# SiLPA_HE_RF_detector.net
KiCad netlist of a schematic drawn in Altium Designer
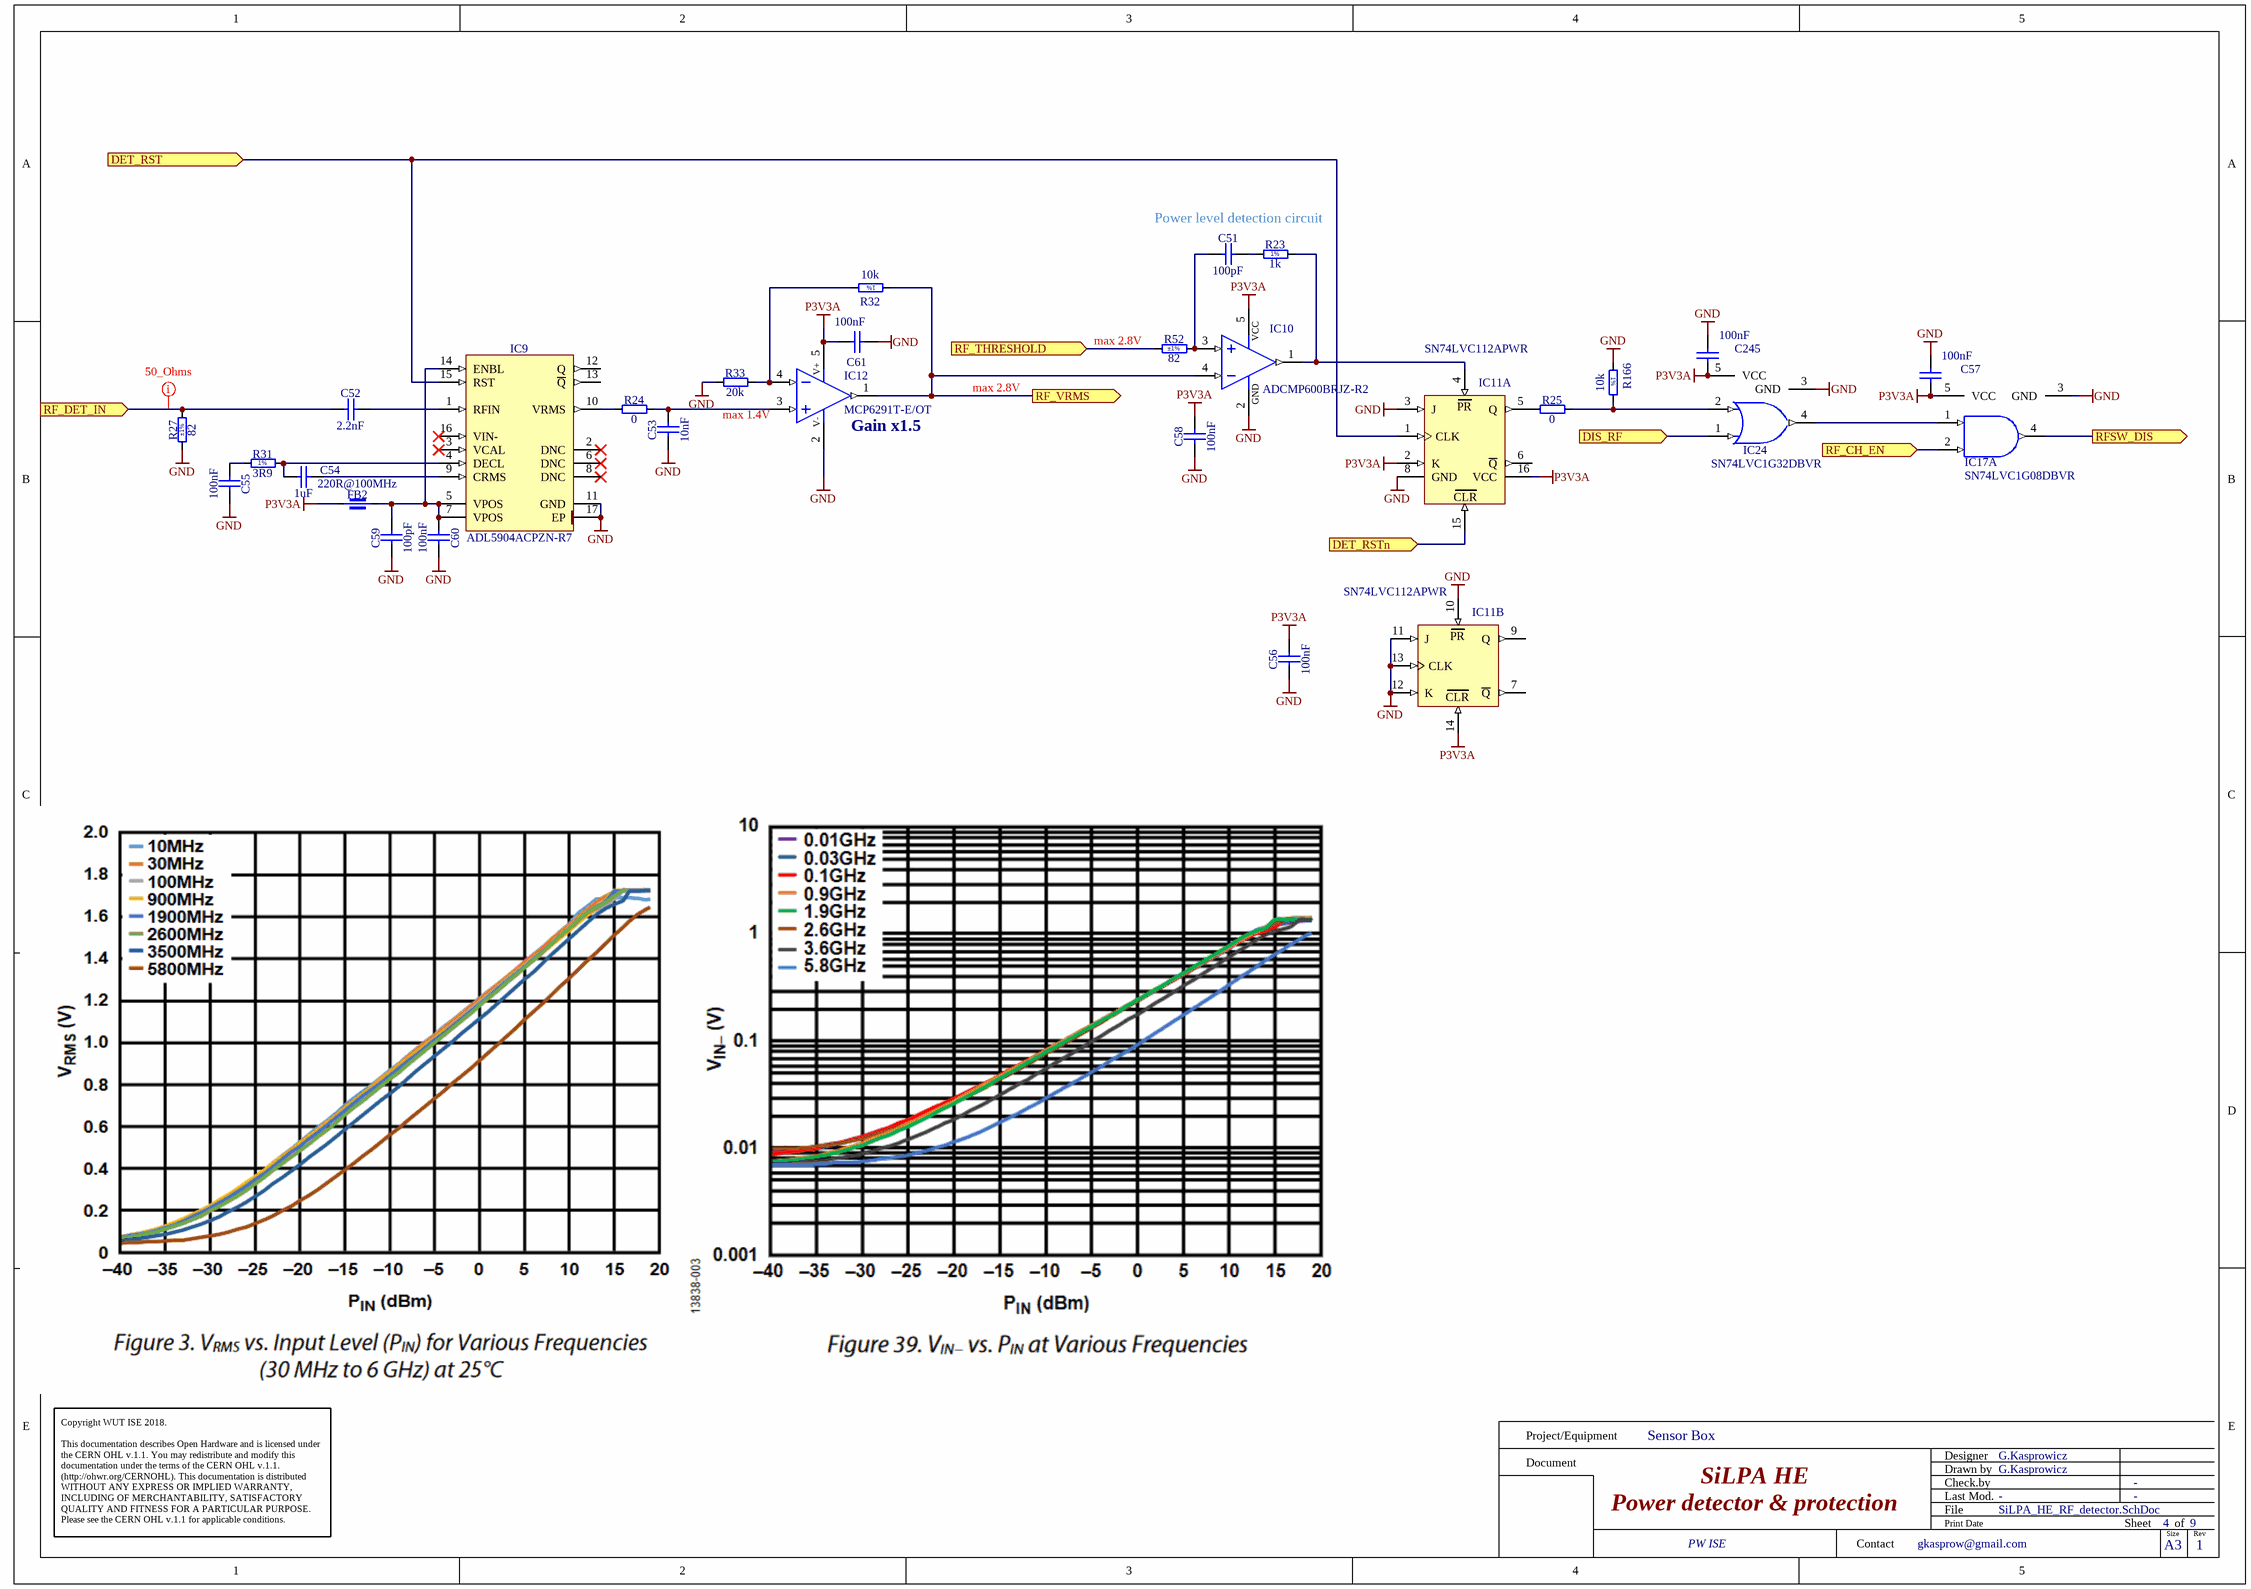
[diagram p0: SiLPA_HE_RF_detector.SchDoc]

(export (version "E")
  (design (tool "Eeschema 10.0.6"))
  (components
    (comp (ref "C51")
      (value "100pF")
      (footprint "CAPC1005X55N")
      (description "Non-polarised capacitor")
      (fields
        (field (name "PART NUMBER") "CC0402_100PF_50V_5%_C0G")
        (field (name "VOLTAGE") "50V")
        (field (name "AUTHOR") "CERN DEM JLC")
      )
      (libsource (lib "Capacitors") (part "Capacitor - non polarized"))
    )
    (comp (ref "C52")
      (value "2.2nF")
      (footprint "CAPC1608X87N")
      (description "Non-polarised capacitor")
      (fields
        (field (name "MANUFACTURER") "GENERIC")
        (field (name "MANUFACTURER PART NUMBER") "CC0603_2.2NF_50V_5%_C0G")
        (field (name "AUTHOR") "CERN DEM JMW")
      )
      (libsource (lib "Capacitors") (part "Capacitor - non polarized"))
    )
    (comp (ref "C53")
      (value "10nF")
      (footprint "CAPC1005X55N")
      (description "Non-polarised capacitor")
      (fields
        (field (name "MANUFACTURER") "GENERIC")
        (field (name "MANUFACTURER PART NUMBER") "CC0402_10NF_25V_10%_X7R")
        (field (name "AUTHOR") "CERN DEM JLC")
      )
      (libsource (lib "Capacitors") (part "Capacitor - non polarized"))
    )
    (comp (ref "C54")
      (value "1uF")
      (footprint "CAPC1608X87N")
      (description "Non-polarised capacitor")
      (fields
        (field (name "PART NUMBER") "CC0603_1UF_25V_10%_X7R")
        (field (name "VOLTAGE") "25V")
        (field (name "AUTHOR") "CERN DEM JLC")
      )
      (libsource (lib "SiLPA_HE") (part "CC0603_1UF_25V_10%_X7R"))
    )
    (comp (ref "C55")
      (value "100nF")
      (footprint "CAPC1005X55N")
      (description "Non-polarised capacitor")
      (fields
        (field (name "MANUFACTURER") "GENERIC")
        (field (name "MANUFACTURER PART NUMBER") "CC0402_100NF_50V_10%_X7R")
        (field (name "AUTHOR") "CERN DEM MR")
      )
      (libsource (lib "Capacitors") (part "Capacitor - non polarized"))
    )
    (comp (ref "C56")
      (value "100nF")
      (footprint "CAPC1005X55N")
      (description "Non-polarised capacitor")
      (fields
        (field (name "PART NUMBER") "CC0402_100NF_16V_10%_X5R")
        (field (name "VOLTAGE") "16V")
        (field (name "AUTHOR") "CERN DEM JLC")
      )
      (libsource (lib "Capacitors") (part "Capacitor - non polarized"))
    )
    (comp (ref "C57")
      (value "100nF")
      (footprint "CAPC1005X55N")
      (description "Non-polarised capacitor")
      (fields
        (field (name "PART NUMBER") "CC0402_100NF_16V_10%_X5R")
        (field (name "VOLTAGE") "16V")
        (field (name "AUTHOR") "CERN DEM JLC")
      )
      (libsource (lib "Capacitors") (part "Capacitor - non polarized"))
    )
    (comp (ref "C58")
      (value "100nF")
      (footprint "CAPC1005X55N")
      (description "Non-polarised capacitor")
      (fields
        (field (name "PART NUMBER") "CC0402_100NF_16V_10%_X5R")
        (field (name "VOLTAGE") "16V")
        (field (name "AUTHOR") "CERN DEM JLC")
      )
      (libsource (lib "Capacitors") (part "Capacitor - non polarized"))
    )
    (comp (ref "C59")
      (value "100pF")
      (footprint "CAPC1005X55N")
      (description "Non-polarised capacitor")
      (fields
        (field (name "PART NUMBER") "CC0402_100PF_50V_5%_C0G")
        (field (name "VOLTAGE") "50V")
        (field (name "AUTHOR") "CERN DEM JLC")
      )
      (libsource (lib "Capacitors") (part "Capacitor - non polarized"))
    )
    (comp (ref "C60")
      (value "100nF")
      (footprint "CAPC1005X55N")
      (description "Non-polarised capacitor")
      (fields
        (field (name "MANUFACTURER") "GENERIC")
        (field (name "MANUFACTURER PART NUMBER") "CC0402_100NF_50V_10%_X7R")
        (field (name "AUTHOR") "CERN DEM MR")
      )
      (libsource (lib "Capacitors") (part "Capacitor - non polarized"))
    )
    (comp (ref "C61")
      (value "100nF")
      (footprint "CAPC1005X55N")
      (description "Non-polarised capacitor")
      (fields
        (field (name "MANUFACTURER") "GENERIC")
        (field (name "MANUFACTURER PART NUMBER") "CC0402_100NF_16V_10%_X5R")
        (field (name "AUTHOR") "CERN DEM JLC")
      )
      (libsource (lib "Capacitors") (part "Capacitor - non polarized"))
    )
    (comp (ref "C245")
      (value "100nF")
      (footprint "CAPC1005X55N")
      (description "Non-polarised capacitor")
      (fields
        (field (name "PART NUMBER") "CC0402_100NF_16V_10%_X5R")
        (field (name "VOLTAGE") "16V")
        (field (name "AUTHOR") "CERN DEM JLC")
      )
      (libsource (lib "Capacitors") (part "Capacitor - non polarized"))
    )
    (comp (ref "FB2")
      (value "220R@100MHz")
      (footprint "INDC1005X55N")
      (fields
        (field (name "PART NUMBER") "IND0402_MURATA_BLM15HB221SN1")
        (field (name "POWER") "250mA")
        (field (name "TOLERANCE") "±25%")
        (field (name "AUTHOR") "CERN DEM JLC")
      )
      (libsource (lib "Inductors & Transformers") (part "Ferrite Bead"))
    )
    (comp (ref "IC9")
      (value "ADL5904ACPZN-R7")
      (footprint "QFN50P300X300X80-17N-S175")
      (description "DC to 6 GHz, 45 dB TruPwr Detector With Envelope Threshold Detection")
      (fields (field (name "MANUFACTURER") "ANALOG DEVICES") (field (name "AUTHOR") "CERN DEM MR"))
      (libsource (lib "ICs And Semiconductors") (part "ADL5904"))
    )
    (comp (ref "IC10")
      (value "ADCMP600BRJZ-R2")
      (footprint "SOT95P280X145-5N")
      (description "Rail-to-Rail, Very Fast, 2.5 V to 5.5 V Single-Supply TTL/CMOS Comparator")
      (fields (field (name "MANUFACTURER") "ANALOG DEVICES") (field (name "AUTHOR") "CERN DEM JLC"))
      (libsource (lib "ICs And Semiconductors") (part "ADCMP600"))
    )
    (comp (ref "IC11")
      (value "SN74LVC112APWR")
      (footprint "SOP65P640X120-16N")
      (description "Dual Negative-Edge-Triggered J-K Flip-Flop With Clear And Preset")
      (fields (field (name "MANUFACTURER") "TEXAS INSTRUMENTS") (field (name "AUTHOR") "CERN DEM JLC"))
      (libsource (lib "ICS-logic") (part "74LVC112APWR"))
    )
    (comp (ref "IC12")
      (value "MCP6291T-E/OT")
      (footprint "SOT95P270X145-5N")
      (description "Operational Amplifier")
      (fields (field (name "MANUFACTURER") "MICROCHIP TECHNOLOGY") (field (name "AUTHOR") "CERN DEM BC"))
      (libsource (lib "ICs And Semiconductors") (part "Operational Amplifier Type7"))
    )
    (comp (ref "IC17")
      (value "SN74LVC1G08DBVR")
      (footprint "DBV0005A_L")
      (description "Single 2-Input Positive-AND Gate, DBV0005A, LARGE T&R")
      (fields
        (field (name "GENERIC PART NUMBER") "SN74LVC1G08")
        (field (name "MANUFACTURER") "Texas Instruments")
      )
      (libsource (lib "Altium Content Vault") (part "TI-SN74XXX1X08-5"))
    )
    (comp (ref "IC24")
      (value "SN74LVC1G32DBVR")
      (footprint "SOT95P280X145-5N")
      (description "Single 2-Input Positive-OR Gate")
      (fields (field (name "MANUFACTURER") "TEXAS INSTRUMENTS") (field (name "AUTHOR") "CERN DEM JLC"))
      (libsource (lib "ICs And Semiconductors") (part "741G32"))
    )
    (comp (ref "R23")
      (value "1k")
      (footprint "RESC1005X40N")
      (description "Resistor - 1%")
      (fields
        (field (name "PART NUMBER") "R0402_1K_1%_0.0625W_100PPM")
        (field (name "POWER") "0.0625W")
        (field (name "AUTHOR") "CERN DEM JLC")
      )
      (libsource (lib "Resistors") (part "Resistor - 1%"))
    )
    (comp (ref "R24")
      (value "0")
      (footprint "RESC1005X40N")
      (description "Resistor")
      (fields
        (field (name "MANUFACTURER") "GENERIC")
        (field (name "MANUFACTURER PART NUMBER") "R0402_0R_JUMPER")
        (field (name "AUTHOR") "CERN DEM JLC")
      )
      (libsource (lib "Resistors") (part "Resistor"))
    )
    (comp (ref "R25")
      (value "0")
      (footprint "RESC1608X55N")
      (description "Resistor")
      (fields
        (field (name "PART NUMBER") "R0603_0R_JUMPER")
        (field (name "MANUFACTURER") "GENERIC")
        (field (name "AUTHOR") "CERN DEM JLC")
      )
      (libsource (lib "Resistors") (part "Resistor"))
    )
    (comp (ref "R27")
      (value "82")
      (footprint "RESC1608X55N")
      (description "Resistor - 1%")
      (fields
        (field (name "TOLERANCE") "±1%")
        (field (name "PART NUMBER") "R0603_82R_1%_0.1W_100PPM")
        (field (name "POWER") "0.1W")
        (field (name "AUTHOR") "CERN DEM JLC")
      )
      (libsource (lib "") (part "Resistor - 1%_1"))
    )
    (comp (ref "R31")
      (value "3R9")
      (footprint "RESC1005X40N")
      (description "Resistor - 1%")
      (fields
        (field (name "PART NUMBER") "R0402_3R9_1%_0.0625W_200PPM")
        (field (name "POWER") "0.0625W")
        (field (name "AUTHOR") "CERN DEM JLC")
      )
      (libsource (lib "Resistors") (part "Resistor - 1%"))
    )
    (comp (ref "R32")
      (value "10k")
      (footprint "RESC1005X40N")
      (description "Resistor - 1%")
      (fields
        (field (name "MANUFACTURER") "GENERIC")
        (field (name "MANUFACTURER PART NUMBER") "R0402_10K_1%_0.0625W_100PPM")
        (field (name "AUTHOR") "CERN DEM JLC")
      )
      (libsource (lib "Resistors") (part "Resistor - 1%"))
    )
    (comp (ref "R33")
      (value "20k")
      (footprint "RESC1005X40N")
      (description "Resistor - 1%")
      (fields
        (field (name "PART NUMBER") "R0402_20K_1%_0.0625W_100PPM")
        (field (name "POWER") "0.0625W")
        (field (name "AUTHOR") "CERN DEM JLC")
      )
      (libsource (lib "Resistors") (part "Resistor - 1%"))
    )
    (comp (ref "R52")
      (value "82")
      (footprint "RESC1005X40N")
      (description "Resistor - 1%")
      (fields
        (field (name "TOLERANCE") "±1%")
        (field (name "PART NUMBER") "R0402_82R_1%_0.0625W_100PPM")
        (field (name "POWER") "0.0625W")
        (field (name "AUTHOR") "CERN DEM JLC")
      )
      (libsource (lib "Resistors") (part "Resistor - 1%"))
    )
    (comp (ref "R166")
      (value "10k")
      (footprint "RESC1005X40N")
      (description "Resistor - 1%")
      (fields
        (field (name "MANUFACTURER") "GENERIC")
        (field (name "MANUFACTURER PART NUMBER") "R0402_10K_1%_0.0625W_100PPM")
        (field (name "AUTHOR") "CERN DEM JLC")
      )
      (libsource (lib "Resistors") (part "Resistor - 1%"))
    )
  )
  (nets
    (net (code "1") (name "/DET_RST") (class "Default")
      (node (ref "IC11") (pin "1") (pinfunction "CLK_1") (pintype "input"))
      (node (ref "IC9") (pin "15") (pinfunction "RST_15") (pintype "input"))
    )
    (net (code "2") (name "/DET_RSTn") (class "Default")
      (node (ref "IC11") (pin "15") (pinfunction "~{CLR}_15") (pintype "input"))
    )
    (net (code "3") (name "/DIS_RF") (class "Default")
      (node (ref "IC24") (pin "1") (pinfunction "A_1") (pintype "input"))
    )
    (net (code "4") (name "/RFSW_DIS") (class "Default")
      (node (ref "IC17") (pin "4") (pinfunction "Y_4") (pintype "output"))
    )
    (net (code "5") (name "/RF_CH_EN") (class "Default")
      (node (ref "IC17") (pin "2") (pinfunction "B_2") (pintype "input"))
    )
    (net (code "6") (name "/RF_DET_IN") (class "Default")
      (node (ref "C52") (pin "1") (pinfunction "1_1") (pintype "passive"))
      (node (ref "R27") (pin "2") (pinfunction "2_2") (pintype "passive"))
    )
    (net (code "7") (name "/RF_THRESHOLD") (class "Default")
      (node (ref "R52") (pin "1") (pinfunction "1_1") (pintype "passive"))
    )
    (net (code "8") (name "/RF_VRMS") (class "Default")
      (node (ref "IC10") (pin "4") (pinfunction "VN_4") (pintype "input"))
      (node (ref "IC12") (pin "1") (pinfunction "OUT_1") (pintype "output"))
      (node (ref "R32") (pin "1") (pinfunction "1_1") (pintype "passive"))
    )
    (net (code "9") (name "GND") (class "Default")
      (node (ref "C245") (pin "2") (pinfunction "2_2") (pintype "passive"))
      (node (ref "C53") (pin "1") (pinfunction "1_1") (pintype "passive"))
      (node (ref "C55") (pin "2") (pinfunction "2_2") (pintype "passive"))
      (node (ref "C56") (pin "1") (pinfunction "1_1") (pintype "passive"))
      (node (ref "C57") (pin "2") (pinfunction "2_2") (pintype "passive"))
      (node (ref "C58") (pin "1") (pinfunction "1_1") (pintype "passive"))
      (node (ref "C59") (pin "1") (pinfunction "1_1") (pintype "passive"))
      (node (ref "C60") (pin "2") (pinfunction "2_2") (pintype "passive"))
      (node (ref "C61") (pin "1") (pinfunction "1_1") (pintype "passive"))
      (node (ref "IC10") (pin "2") (pinfunction "GND_2") (pintype "power_in"))
      (node (ref "IC11") (pin "10") (pinfunction "~{PRE}_10") (pintype "input"))
      (node (ref "IC11") (pin "11") (pinfunction "J_11") (pintype "input"))
      (node (ref "IC11") (pin "12") (pinfunction "K_12") (pintype "input"))
      (node (ref "IC11") (pin "13") (pinfunction "CLK_13") (pintype "input"))
      (node (ref "IC11") (pin "3") (pinfunction "J_3") (pintype "input"))
      (node (ref "IC11") (pin "8") (pinfunction "GND_8") (pintype "power_in"))
      (node (ref "IC12") (pin "2") (pinfunction "V-_2") (pintype "power_in"))
      (node (ref "IC17") (pin "3") (pinfunction "GND_3") (pintype "power_in"))
      (node (ref "IC24") (pin "3") (pinfunction "GND_3") (pintype "power_in"))
      (node (ref "IC9") (pin "11") (pinfunction "GND_11") (pintype "power_in"))
      (node (ref "IC9") (pin "17") (pinfunction "EP_17") (pintype "power_in"))
      (node (ref "R166") (pin "1") (pinfunction "1_1") (pintype "passive"))
      (node (ref "R27") (pin "1") (pinfunction "1_1") (pintype "passive"))
      (node (ref "R33") (pin "1") (pinfunction "1_1") (pintype "passive"))
    )
    (net (code "10") (name "Net-(C51-Pad2)") (class "Default")
      (node (ref "C51") (pin "2") (pinfunction "2_2") (pintype "passive"))
      (node (ref "R23") (pin "1") (pinfunction "1_1") (pintype "passive"))
    )
    (net (code "11") (name "Net-(C55-Pad1)") (class "Default")
      (node (ref "C55") (pin "1") (pinfunction "1_1") (pintype "passive"))
      (node (ref "R31") (pin "1") (pinfunction "1_1") (pintype "passive"))
    )
    (net (code "12") (name "Net-(IC9-CRMS)") (class "Default")
      (node (ref "C54") (pin "2") (pinfunction "2_2") (pintype "passive"))
      (node (ref "IC9") (pin "9") (pinfunction "CRMS_9") (pintype "input"))
    )
    (net (code "13") (name "Net-(IC9-DECL)") (class "Default")
      (node (ref "C54") (pin "1") (pinfunction "1_1") (pintype "passive"))
      (node (ref "IC9") (pin "4") (pinfunction "DECL_4") (pintype "input"))
      (node (ref "R31") (pin "2") (pinfunction "2_2") (pintype "passive"))
    )
    (net (code "14") (name "Net-(IC9-ENBL)") (class "Default")
      (node (ref "C59") (pin "2") (pinfunction "2_2") (pintype "passive"))
      (node (ref "C60") (pin "1") (pinfunction "1_1") (pintype "passive"))
      (node (ref "FB2") (pin "2") (pinfunction "2_2") (pintype "passive"))
      (node (ref "IC9") (pin "14") (pinfunction "ENBL_14") (pintype "input"))
      (node (ref "IC9") (pin "5") (pinfunction "VPOS_5") (pintype "power_in"))
      (node (ref "IC9") (pin "7") (pinfunction "VPOS_7") (pintype "power_in"))
    )
    (net (code "15") (name "Net-(IC9-RFIN)") (class "Default")
      (node (ref "C52") (pin "2") (pinfunction "2_2") (pintype "passive"))
      (node (ref "IC9") (pin "1") (pinfunction "RFIN_1") (pintype "input"))
    )
    (net (code "16") (name "Net-(IC9-VRMS)") (class "Default")
      (node (ref "IC9") (pin "10") (pinfunction "VRMS_10") (pintype "output"))
      (node (ref "R24") (pin "1") (pinfunction "1_1") (pintype "passive"))
    )
    (net (code "17") (name "Net-(IC10-VP)") (class "Default")
      (node (ref "C51") (pin "1") (pinfunction "1_1") (pintype "passive"))
      (node (ref "IC10") (pin "3") (pinfunction "VP_3") (pintype "input"))
      (node (ref "R52") (pin "2") (pinfunction "2_2") (pintype "passive"))
    )
    (net (code "18") (name "Net-(IC10-q)") (class "Default")
      (node (ref "IC10") (pin "1") (pinfunction "q_1") (pintype "output"))
      (node (ref "IC11") (pin "4") (pinfunction "~{PRE}_4") (pintype "input"))
      (node (ref "R23") (pin "2") (pinfunction "2_2") (pintype "passive"))
    )
    (net (code "19") (name "Net-(IC11A-Q)") (class "Default")
      (node (ref "IC11") (pin "5") (pinfunction "Q_5") (pintype "output"))
      (node (ref "R25") (pin "1") (pinfunction "1_1") (pintype "passive"))
    )
    (net (code "20") (name "Net-(IC12-IN+)") (class "Default")
      (node (ref "C53") (pin "2") (pinfunction "2_2") (pintype "passive"))
      (node (ref "IC12") (pin "3") (pinfunction "IN+_3") (pintype "input"))
      (node (ref "R24") (pin "2") (pinfunction "2_2") (pintype "passive"))
    )
    (net (code "21") (name "Net-(IC12-IN-)") (class "Default")
      (node (ref "IC12") (pin "4") (pinfunction "IN-_4") (pintype "input"))
      (node (ref "R32") (pin "2") (pinfunction "2_2") (pintype "passive"))
      (node (ref "R33") (pin "2") (pinfunction "2_2") (pintype "passive"))
    )
    (net (code "22") (name "Net-(IC17A-A)") (class "Default")
      (node (ref "IC17") (pin "1") (pinfunction "A_1") (pintype "input"))
      (node (ref "IC24") (pin "4") (pinfunction "Y_4") (pintype "output"))
    )
    (net (code "23") (name "Net-(IC24-B)") (class "Default")
      (node (ref "IC24") (pin "2") (pinfunction "B_2") (pintype "input"))
      (node (ref "R166") (pin "2") (pinfunction "2_2") (pintype "passive"))
      (node (ref "R25") (pin "2") (pinfunction "2_2") (pintype "passive"))
    )
    (net (code "24") (name "P3V3A") (class "Default")
      (node (ref "C245") (pin "1") (pinfunction "1_1") (pintype "passive"))
      (node (ref "C56") (pin "2") (pinfunction "2_2") (pintype "passive"))
      (node (ref "C57") (pin "1") (pinfunction "1_1") (pintype "passive"))
      (node (ref "C58") (pin "2") (pinfunction "2_2") (pintype "passive"))
      (node (ref "C61") (pin "2") (pinfunction "2_2") (pintype "passive"))
      (node (ref "FB2") (pin "1") (pinfunction "1_1") (pintype "passive"))
      (node (ref "IC10") (pin "5") (pinfunction "VCC_5") (pintype "power_in"))
      (node (ref "IC11") (pin "14") (pinfunction "~{CLR}_14") (pintype "input"))
      (node (ref "IC11") (pin "16") (pinfunction "VCC_16") (pintype "power_in"))
      (node (ref "IC11") (pin "2") (pinfunction "K_2") (pintype "input"))
      (node (ref "IC12") (pin "5") (pinfunction "V+_5") (pintype "power_in"))
      (node (ref "IC17") (pin "5") (pinfunction "VCC_5") (pintype "power_in"))
      (node (ref "IC24") (pin "5") (pinfunction "VCC_5") (pintype "power_in"))
    )
    (net (code "25") (name "unconnected-(IC9-DNC-Pad2)") (class "Default")
      (node (ref "IC9") (pin "2") (pinfunction "DNC_2") (pintype "passive+no_connect"))
    )
    (net (code "26") (name "unconnected-(IC9-DNC-Pad6)") (class "Default")
      (node (ref "IC9") (pin "6") (pinfunction "DNC_6") (pintype "passive+no_connect"))
    )
    (net (code "27") (name "unconnected-(IC9-DNC-Pad8)") (class "Default")
      (node (ref "IC9") (pin "8") (pinfunction "DNC_8") (pintype "passive+no_connect"))
    )
    (net (code "28") (name "unconnected-(IC9-Q-Pad12)") (class "Default")
      (node (ref "IC9") (pin "12") (pinfunction "Q_12") (pintype "output"))
    )
    (net (code "29") (name "unconnected-(IC9-VCAL-Pad3)") (class "Default")
      (node (ref "IC9") (pin "3") (pinfunction "VCAL_3") (pintype "input+no_connect"))
    )
    (net (code "30") (name "unconnected-(IC9-VIN--Pad16)") (class "Default")
      (node (ref "IC9") (pin "16") (pinfunction "VIN-_16") (pintype "input+no_connect"))
    )
    (net (code "31") (name "unconnected-(IC9-~{Q}-Pad13)") (class "Default")
      (node (ref "IC9") (pin "13") (pinfunction "~{Q}_13") (pintype "output"))
    )
    (net (code "32") (name "unconnected-(IC11A-~{Q}-Pad6)") (class "Default")
      (node (ref "IC11") (pin "6") (pinfunction "~{Q}_6") (pintype "output"))
    )
    (net (code "33") (name "unconnected-(IC11B-Q-Pad9)") (class "Default")
      (node (ref "IC11") (pin "9") (pinfunction "Q_9") (pintype "output"))
    )
    (net (code "34") (name "unconnected-(IC11B-~{Q}-Pad7)") (class "Default")
      (node (ref "IC11") (pin "7") (pinfunction "~{Q}_7") (pintype "output"))
    )
  )
)
